# BLE.net
KiCad netlist of a schematic drawn in Altium Designer
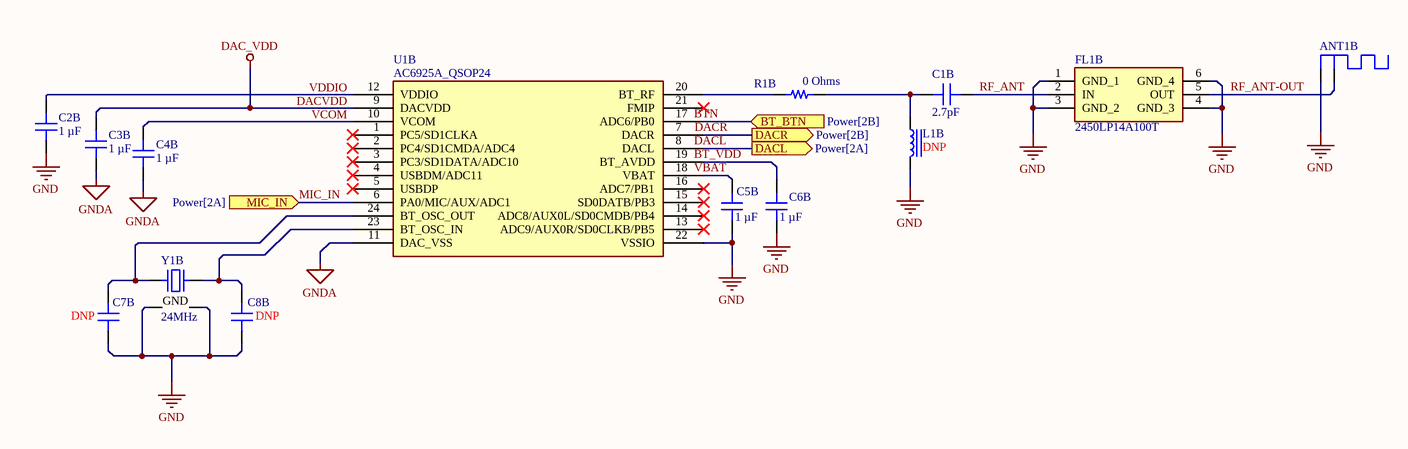
[diagram p0: BLE.SchDoc]

(export (version "E")
  (design (tool "Eeschema 10.0.6"))
  (components
    (comp (ref "ANT1B")
      (value "ANTENNA")
      (footprint "RN-ANT")
      (fields (field (name "MP") "Antenna") (field (name "MF") "Infineon Technologies"))
      (libsource (lib "ANTENNA") (part "ANTENNA"))
    )
    (comp (ref "C1B")
      (value "2.7pF")
      (footprint "CAP 0402_1005")
      (description "CAP CER 2.7PF 25V NP0 0402")
      (fields (field (name "PART NUMBER") "04023A2R7BAT2A") (field (name "MANUFACTURER") "AVX Corporation"))
      (libsource (lib "Postgres Altium Library - altium_library") (part "Capacitor"))
    )
    (comp (ref "C2B")
      (value "1 µF")
      (footprint "CAP 0603_1608")
      (description "CAP CER 1UF 10V Y5V 0603")
      (fields (field (name "PART NUMBER") "CC0603ZRY5V6BB105") (field (name "MANUFACTURER") "Yageo"))
      (libsource (lib "Postgres Altium Library - altium_library") (part "Capacitor"))
    )
    (comp (ref "C3B")
      (value "1 µF")
      (footprint "CAP 0603_1608")
      (description "CAP CER 1UF 10V Y5V 0603")
      (fields (field (name "PART NUMBER") "CC0603ZRY5V6BB105") (field (name "MANUFACTURER") "Yageo"))
      (libsource (lib "Postgres Altium Library - altium_library") (part "Capacitor"))
    )
    (comp (ref "C4B")
      (value "1 µF")
      (footprint "CAP 0603_1608")
      (description "CAP CER 1UF 10V Y5V 0603")
      (fields (field (name "PART NUMBER") "CC0603ZRY5V6BB105") (field (name "MANUFACTURER") "Yageo"))
      (libsource (lib "Postgres Altium Library - altium_library") (part "Capacitor"))
    )
    (comp (ref "C5B")
      (value "1 µF")
      (footprint "CAP 0603_1608")
      (description "CAP CER 1UF 10V Y5V 0603")
      (fields (field (name "PART NUMBER") "CC0603ZRY5V6BB105") (field (name "MANUFACTURER") "Yageo"))
      (libsource (lib "Postgres Altium Library - altium_library") (part "Capacitor"))
    )
    (comp (ref "C6B")
      (value "1 µF")
      (footprint "CAP 0603_1608")
      (description "CAP CER 1UF 10V Y5V 0603")
      (fields (field (name "PART NUMBER") "CC0603ZRY5V6BB105") (field (name "MANUFACTURER") "Yageo"))
      (libsource (lib "Postgres Altium Library - altium_library") (part "Capacitor"))
    )
    (comp (ref "C7B")
      (value "DNP")
      (footprint "CAP 0402_1005")
      (description "CAP CER 10PF 10V C0G/NP0 0402")
      (fields (field (name "PART NUMBER") "885012005007") (field (name "MANUFACTURER") "Würth Elektronik"))
      (libsource (lib "Postgres Altium Library - altium_library") (part "Capacitor"))
    )
    (comp (ref "C8B")
      (value "DNP")
      (footprint "CAP 0402_1005")
      (description "CAP CER 10PF 10V C0G/NP0 0402")
      (fields (field (name "PART NUMBER") "885012005007") (field (name "MANUFACTURER") "Würth Elektronik"))
      (libsource (lib "Postgres Altium Library - altium_library") (part "Capacitor"))
    )
    (comp (ref "FL1B")
      (value "2450LP14A100T")
      (footprint "2450LP14A100T")
      (description "Filter")
      (fields (field (name "MOUSER PART NUMBER") "609-2450LP14A100T"))
      (libsource (lib "2.4 GHz Low Pass Filter") (part "2450LP14A100T"))
    )
    (comp (ref "L1B")
      (value "DNP")
      (footprint "IND 0402_1005 RF WW")
      (description "FIXED IND 1NH 1.36A 45 MOHM SMD")
      (fields (field (name "PART NUMBER") "744765010A") (field (name "TOLERANCE") "±0.2nH"))
      (libsource (lib "Postgres Altium Library - altium_library") (part "Inductor"))
    )
    (comp (ref "R1B")
      (value "0 Ohms")
      (footprint "RES 0402_1005")
      (description "RES SMD 0 OHM JUMPER 1/16W 0402")
      (fields (field (name "PART NUMBER") "AC0402JR-070RL") (field (name "TOLERANCE") "Jumper"))
      (libsource (lib "Postgres Altium Library - altium_library") (part "Resistor"))
    )
    (comp (ref "U1B")
      (value "AC6925A")
      (footprint "AC6925A")
      (description "Bluetooth Audio IC")
      (fields (field (name "MF") "Analog Devices") (field (name "MP") "MAX1092BCEG+"))
      (libsource (lib "JL") (part "AC6925A"))
    )
    (comp (ref "Y1B")
      (value "24MHz")
      (footprint "ABRACON ABM10")
      (description "CRYSTAL 24.0000MHZ 10PF SMD")
      (fields
        (field (name "PART NUMBER") "ABM10-24.000MHZ-E20-T")
        (field (name "MANUFACTURER") "Abracon LLC")
      )
      (libsource (lib "Postgres Altium Library - altium_library") (part "Abracon Crystal ABM10"))
    )
  )
  (nets
    (net (code "1") (name "/BTN") (class "Default")
      (node (ref "U1B") (pin "17") (pinfunction "ADC6/PB0_17") (pintype "passive"))
    )
    (net (code "2") (name "/BT_VDD") (class "Default")
      (node (ref "C6B") (pin "2") (pinfunction "2_2") (pintype "passive"))
      (node (ref "U1B") (pin "19") (pinfunction "BT_AVDD_19") (pintype "passive"))
    )
    (net (code "3") (name "/DACL") (class "Default")
      (node (ref "U1B") (pin "8") (pinfunction "DACL_8") (pintype "passive"))
    )
    (net (code "4") (name "/DACR") (class "Default")
      (node (ref "U1B") (pin "7") (pinfunction "DACR_7") (pintype "passive"))
    )
    (net (code "6") (name "/MIC_IN") (class "Default")
      (node (ref "U1B") (pin "6") (pinfunction "PA0/MIC/AUX/ADC1_6") (pintype "passive"))
    )
    (net (code "7") (name "/RF_ANT") (class "Default")
      (node (ref "C1B") (pin "2") (pinfunction "2_2") (pintype "passive"))
      (node (ref "FL1B") (pin "2") (pinfunction "IN_2") (pintype "passive"))
    )
    (net (code "8") (name "/RF_ANT-OUT") (class "Default")
      (node (ref "ANT1B") (pin "FEED") (pinfunction "FEED_FEED") (pintype "passive"))
      (node (ref "FL1B") (pin "5") (pinfunction "OUT_5") (pintype "passive"))
    )
    (net (code "9") (name "/VBAT") (class "Default")
      (node (ref "C5B") (pin "2") (pinfunction "2_2") (pintype "passive"))
      (node (ref "U1B") (pin "18") (pinfunction "VBAT_18") (pintype "passive"))
    )
    (net (code "12") (name "DAC_VDD") (class "Default")
      (node (ref "C3B") (pin "2") (pinfunction "2_2") (pintype "passive"))
      (node (ref "U1B") (pin "9") (pinfunction "DACVDD_9") (pintype "passive"))
    )
    (net (code "13") (name "GND") (class "Default")
      (node (ref "ANT1B") (pin "GND") (pinfunction "GND_GND") (pintype "passive"))
      (node (ref "C2B") (pin "1") (pinfunction "1_1") (pintype "passive"))
      (node (ref "C5B") (pin "1") (pinfunction "1_1") (pintype "passive"))
      (node (ref "C6B") (pin "1") (pinfunction "1_1") (pintype "passive"))
      (node (ref "C7B") (pin "1") (pinfunction "1_1") (pintype "passive"))
      (node (ref "C8B") (pin "1") (pinfunction "1_1") (pintype "passive"))
      (node (ref "FL1B") (pin "1") (pinfunction "GND_1_1") (pintype "passive"))
      (node (ref "FL1B") (pin "3") (pinfunction "GND_2_3") (pintype "passive"))
      (node (ref "FL1B") (pin "4") (pinfunction "GND_3_4") (pintype "passive"))
      (node (ref "FL1B") (pin "6") (pinfunction "GND_4_6") (pintype "passive"))
      (node (ref "L1B") (pin "2") (pinfunction "2_2") (pintype "passive"))
      (node (ref "U1B") (pin "22") (pinfunction "VSSIO_22") (pintype "passive"))
      (node (ref "Y1B") (pin "2") (pinfunction "GND_2") (pintype "passive"))
      (node (ref "Y1B") (pin "4") (pinfunction "GND_4") (pintype "passive"))
    )
    (net (code "14") (name "GNDA") (class "Default")
      (node (ref "C3B") (pin "1") (pinfunction "1_1") (pintype "passive"))
      (node (ref "C4B") (pin "1") (pinfunction "1_1") (pintype "passive"))
      (node (ref "U1B") (pin "11") (pinfunction "DAC_VSS_11") (pintype "passive"))
    )
    (net (code "15") (name "Net-(C1B-Pad1)") (class "Default")
      (node (ref "C1B") (pin "1") (pinfunction "1_1") (pintype "passive"))
      (node (ref "L1B") (pin "1") (pinfunction "1_1") (pintype "passive"))
      (node (ref "R1B") (pin "2") (pinfunction "2_2") (pintype "passive"))
    )
    (net (code "16") (name "Net-(U1B-BT_OSC_IN)") (class "Default")
      (node (ref "C8B") (pin "2") (pinfunction "2_2") (pintype "passive"))
      (node (ref "U1B") (pin "23") (pinfunction "BT_OSC_IN_23") (pintype "passive"))
      (node (ref "Y1B") (pin "3") (pinfunction "3_3") (pintype "passive"))
    )
    (net (code "17") (name "Net-(U1B-BT_OSC_OUT)") (class "Default")
      (node (ref "C7B") (pin "2") (pinfunction "2_2") (pintype "passive"))
      (node (ref "U1B") (pin "24") (pinfunction "BT_OSC_OUT_24") (pintype "passive"))
      (node (ref "Y1B") (pin "1") (pinfunction "1_1") (pintype "passive"))
    )
    (net (code "18") (name "Net-(U1B-BT_RF)") (class "Default")
      (node (ref "R1B") (pin "1") (pinfunction "1_1") (pintype "passive"))
      (node (ref "U1B") (pin "20") (pinfunction "BT_RF_20") (pintype "passive"))
    )
    (net (code "19") (name "Net-(U1B-VCOM)") (class "Default")
      (node (ref "C4B") (pin "2") (pinfunction "2_2") (pintype "passive"))
      (node (ref "U1B") (pin "10") (pinfunction "VCOM_10") (pintype "passive"))
    )
    (net (code "20") (name "Net-(U1B-VDDIO)") (class "Default")
      (node (ref "C2B") (pin "2") (pinfunction "2_2") (pintype "passive"))
      (node (ref "U1B") (pin "12") (pinfunction "VDDIO_12") (pintype "passive"))
    )
    (net (code "21") (name "unconnected-(U1B-ADC7{slash}PB1-Pad16)") (class "Default")
      (node (ref "U1B") (pin "16") (pinfunction "ADC7/PB1_16") (pintype "passive+no_connect"))
    )
    (net (code "22") (name "unconnected-(U1B-ADC8{slash}AUX0L{slash}SD0CMDB{slash}PB4-Pad14)") (class "Default")
      (node (ref "U1B") (pin "14") (pinfunction "ADC8/AUX0L/SD0CMDB/PB4_14") (pintype "passive+no_connect"))
    )
    (net (code "23") (name "unconnected-(U1B-ADC9{slash}AUX0R{slash}SD0CLKB{slash}PB5-Pad13)") (class "Default")
      (node (ref "U1B") (pin "13") (pinfunction "ADC9/AUX0R/SD0CLKB/PB5_13") (pintype "passive+no_connect"))
    )
    (net (code "24") (name "unconnected-(U1B-FMIP-Pad21)") (class "Default")
      (node (ref "U1B") (pin "21") (pinfunction "FMIP_21") (pintype "passive+no_connect"))
    )
    (net (code "25") (name "unconnected-(U1B-PC3{slash}SD1DATA{slash}ADC10-Pad3)") (class "Default")
      (node (ref "U1B") (pin "3") (pinfunction "PC3/SD1DATA/ADC10_3") (pintype "passive+no_connect"))
    )
    (net (code "26") (name "unconnected-(U1B-PC4{slash}SD1CMDA{slash}ADC4-Pad2)") (class "Default")
      (node (ref "U1B") (pin "2") (pinfunction "PC4/SD1CMDA/ADC4_2") (pintype "passive+no_connect"))
    )
    (net (code "27") (name "unconnected-(U1B-PC5{slash}SD1CLKA-Pad1)") (class "Default")
      (node (ref "U1B") (pin "1") (pinfunction "PC5/SD1CLKA_1") (pintype "passive+no_connect"))
    )
    (net (code "28") (name "unconnected-(U1B-SD0DATB{slash}PB3-Pad15)") (class "Default")
      (node (ref "U1B") (pin "15") (pinfunction "SD0DATB/PB3_15") (pintype "passive+no_connect"))
    )
    (net (code "29") (name "unconnected-(U1B-USBDM{slash}ADC11-Pad4)") (class "Default")
      (node (ref "U1B") (pin "4") (pinfunction "USBDM/ADC11_4") (pintype "passive+no_connect"))
    )
    (net (code "30") (name "unconnected-(U1B-USBDP-Pad5)") (class "Default")
      (node (ref "U1B") (pin "5") (pinfunction "USBDP_5") (pintype "passive+no_connect"))
    )
  )
)
